# SerialRF1_SMD.net
KiCad netlist of a schematic drawn in EAGLE
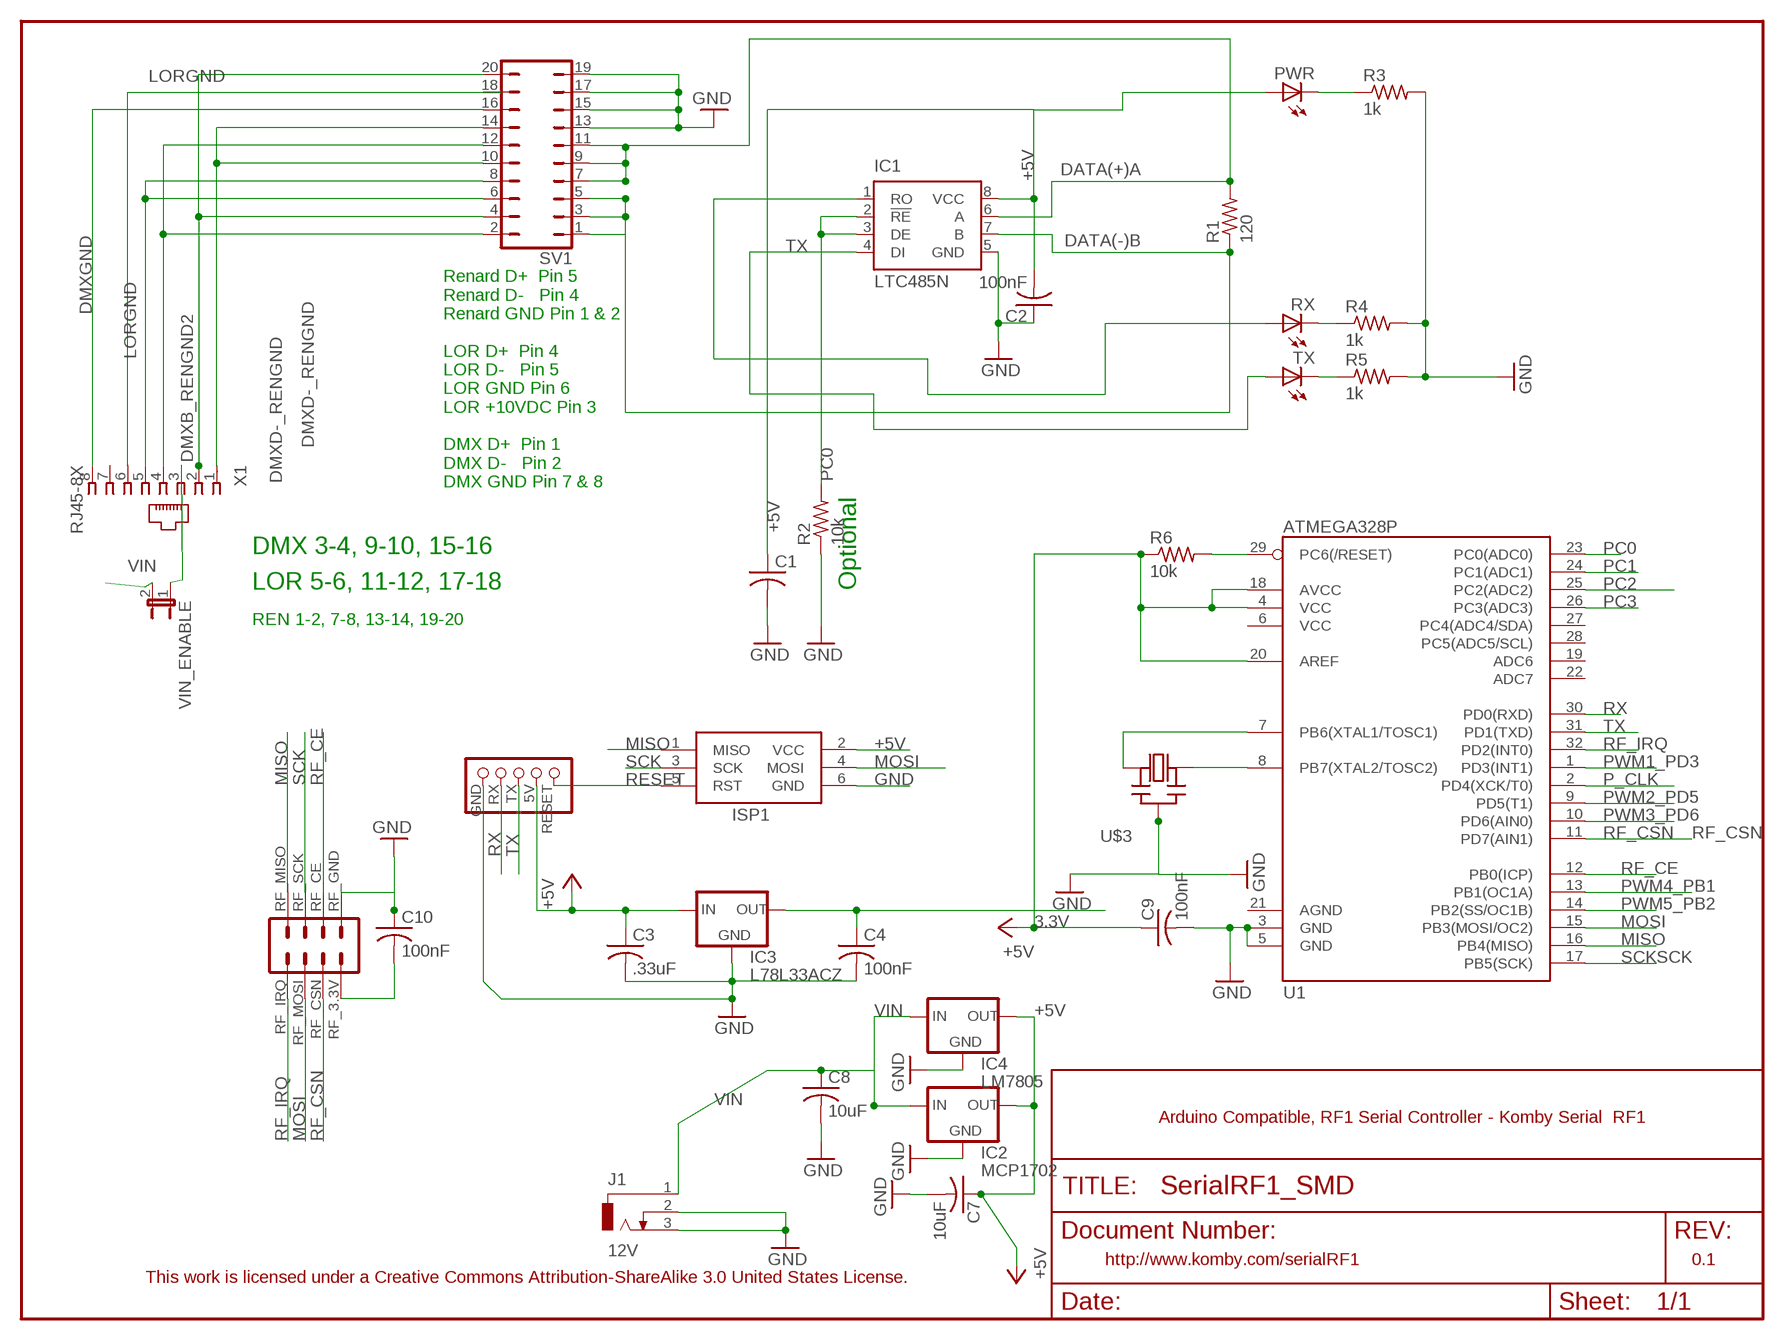
[diagram p0: schematic, sheet 1]

(export (version "E")
  (design (tool "Eeschema 10.0.6"))
  (components
    (comp (ref "C1")
      (value "C-USC0805K")
      (footprint "eagle-import:C0805K")
      (libsource (lib "eagle-import") (part "C-USC0805K"))
    )
    (comp (ref "C2")
      (value "100nF")
      (footprint "eagle-import:C0805K")
      (libsource (lib "eagle-import") (part "C-USC0805K"))
    )
    (comp (ref "C3")
      (value ".33uF")
      (footprint "eagle-import:C0805K")
      (libsource (lib "eagle-import") (part "C-USC0805K"))
    )
    (comp (ref "C4")
      (value "100nF")
      (footprint "eagle-import:C0805K")
      (libsource (lib "eagle-import") (part "C-USC0805K"))
    )
    (comp (ref "C7")
      (value "10uF")
      (footprint "eagle-import:C0805K")
      (libsource (lib "eagle-import") (part "C-USC0805K"))
    )
    (comp (ref "C8")
      (value "10uF")
      (footprint "eagle-import:C0805K")
      (libsource (lib "eagle-import") (part "C-USC0805K"))
    )
    (comp (ref "C9")
      (value "100nF")
      (footprint "eagle-import:C0805K")
      (libsource (lib "eagle-import") (part "C-USC0805K"))
    )
    (comp (ref "C10")
      (value "100nF")
      (footprint "eagle-import:C0805K")
      (libsource (lib "eagle-import") (part "C-USC0805K"))
    )
    (comp (ref "IC1")
      (value "LTC485N")
      (footprint "eagle-import:DIL08")
      (libsource (lib "eagle-import") (part "LTC485N"))
    )
    (comp (ref "IC2")
      (value "MCP1702")
      (footprint "eagle-import:TO92")
      (libsource (lib "eagle-import") (part "MCP1700TRI"))
    )
    (comp (ref "IC3")
      (value "L78L33ACZ")
      (footprint "eagle-import:78LXX")
      (libsource (lib "eagle-import") (part "78LXX"))
    )
    (comp (ref "IC4")
      (value "LM7805")
      (footprint "eagle-import:TO220-IGO")
      (libsource (lib "eagle-import") (part "V_REG_78XXSINK"))
    )
    (comp (ref "ISP1")
      (value "AVRISP-6")
      (footprint "eagle-import:AVRISP")
      (libsource (lib "eagle-import") (part "AVRISP-6"))
    )
    (comp (ref "J1")
      (value "12V")
      (footprint "eagle-import:DCJ0303")
      (libsource (lib "eagle-import") (part "DCJ0303"))
    )
    (comp (ref "PWR")
      (value "LEDSML0805")
      (footprint "eagle-import:SML0805")
      (libsource (lib "eagle-import") (part "LEDSML0805"))
    )
    (comp (ref "R1")
      (value "120")
      (footprint "eagle-import:R0805W")
      (libsource (lib "eagle-import") (part "R-US_R0805W"))
    )
    (comp (ref "R2")
      (value "10k")
      (footprint "eagle-import:R0805W")
      (libsource (lib "eagle-import") (part "R-US_R0805W"))
    )
    (comp (ref "R3")
      (value "1k")
      (footprint "eagle-import:M0805")
      (libsource (lib "eagle-import") (part "R-US_M0805"))
    )
    (comp (ref "R4")
      (value "1k")
      (footprint "eagle-import:M0805")
      (libsource (lib "eagle-import") (part "R-US_M0805"))
    )
    (comp (ref "R5")
      (value "1k")
      (footprint "eagle-import:M0805")
      (libsource (lib "eagle-import") (part "R-US_M0805"))
    )
    (comp (ref "R6")
      (value "10k")
      (footprint "eagle-import:R0805")
      (libsource (lib "eagle-import") (part "R-US_R0805"))
    )
    (comp (ref "RX")
      (value "LEDSML0805")
      (footprint "eagle-import:SML0805")
      (libsource (lib "eagle-import") (part "LEDSML0805"))
    )
    (comp (ref "SV1")
      (value "JP10Q")
      (footprint "eagle-import:JP10Q")
      (libsource (lib "eagle-import") (part "JP10Q"))
    )
    (comp (ref "TX")
      (value "LEDSML0805")
      (footprint "eagle-import:SML0805")
      (libsource (lib "eagle-import") (part "LEDSML0805"))
    )
    (comp (ref "U$3")
      (value "CERMOSCILL-THM")
      (footprint "eagle-import:CERM_OSC")
      (libsource (lib "eagle-import") (part "CERMOSCILL-THM"))
    )
    (comp (ref "U$4")
      (value "KOMBY_TTL_SERIAL")
      (footprint "eagle-import:KOMBY_SERIAL_FOOTPRINT")
      (libsource (lib "eagle-import") (part "KOMBY_TTL_SERIAL"))
    )
    (comp (ref "U$6")
      (value "NRF24L01_HEADER")
      (footprint "eagle-import:NRF24L01")
      (libsource (lib "eagle-import") (part "NRF24L01_HEADER"))
    )
    (comp (ref "U1")
      (value "ATMEGA328P")
      (footprint "eagle-import:TQFP32-08")
      (libsource (lib "eagle-import") (part "ATMEGA328_SMT"))
    )
    (comp (ref "VIN_ENABLE")
      (value "JP1E")
      (footprint "eagle-import:JP1")
      (libsource (lib "eagle-import") (part "JP1E"))
    )
    (comp (ref "X1")
      (value "RJ45-8X")
      (footprint "eagle-import:RJ45-NO-SHIELD")
      (libsource (lib "eagle-import") (part "RJ45-8X"))
    )
  )
  (nets
    (net (code "1") (name "+5V") (class "Default")
      (node (ref "C1") (pin "1") (pinfunction "1_1") (pintype "passive"))
      (node (ref "C2") (pin "2") (pinfunction "2_2") (pintype "passive"))
      (node (ref "C3") (pin "1") (pinfunction "1_1") (pintype "passive"))
      (node (ref "C7") (pin "1") (pinfunction "1_1") (pintype "passive"))
      (node (ref "C9") (pin "1") (pinfunction "1_1") (pintype "passive"))
      (node (ref "IC1") (pin "8") (pinfunction "VCC_8") (pintype "input"))
      (node (ref "IC2") (pin "3") (pinfunction "OUT_3") (pintype "passive"))
      (node (ref "IC3") (pin "IN") (pinfunction "IN_IN") (pintype "input"))
      (node (ref "IC4") (pin "OUT") (pinfunction "OUT_OUT") (pintype "output"))
      (node (ref "ISP1") (pin "2") (pinfunction "VCC_2") (pintype "power_in"))
      (node (ref "PWR") (pin "A") (pinfunction "A_A") (pintype "passive"))
      (node (ref "R6") (pin "1") (pinfunction "1_1") (pintype "passive"))
      (node (ref "U$4") (pin "5V") (pinfunction "5V_5V") (pintype "passive"))
      (node (ref "U1") (pin "18") (pinfunction "AVCC_18") (pintype "bidirectional"))
      (node (ref "U1") (pin "20") (pinfunction "AREF_20") (pintype "bidirectional"))
      (node (ref "U1") (pin "4") (pinfunction "VCC_4") (pintype "bidirectional"))
    )
    (net (code "2") (name "/3.3V") (class "Default")
      (node (ref "C4") (pin "1") (pinfunction "1_1") (pintype "passive"))
      (node (ref "IC3") (pin "OUT") (pinfunction "OUT_OUT") (pintype "passive"))
    )
    (net (code "3") (name "/DATA(+)A") (class "Default")
      (node (ref "IC1") (pin "6") (pinfunction "A_6") (pintype "bidirectional"))
      (node (ref "R1") (pin "2") (pinfunction "2_2") (pintype "passive"))
      (node (ref "SV1") (pin "11") (pinfunction "11_11") (pintype "passive"))
      (node (ref "SV1") (pin "7") (pinfunction "7_7") (pintype "passive"))
      (node (ref "SV1") (pin "9") (pinfunction "9_9") (pintype "passive"))
    )
    (net (code "4") (name "/DATA(-)B") (class "Default")
      (node (ref "IC1") (pin "7") (pinfunction "B_7") (pintype "bidirectional"))
      (node (ref "R1") (pin "1") (pinfunction "1_1") (pintype "passive"))
      (node (ref "SV1") (pin "1") (pinfunction "1_1") (pintype "passive"))
      (node (ref "SV1") (pin "3") (pinfunction "3_3") (pintype "passive"))
      (node (ref "SV1") (pin "5") (pinfunction "5_5") (pintype "passive"))
    )
    (net (code "5") (name "/DMXB_RENGND2") (class "Default")
      (node (ref "SV1") (pin "20") (pinfunction "20_20") (pintype "passive"))
      (node (ref "SV1") (pin "4") (pinfunction "4_4") (pintype "passive"))
      (node (ref "X1") (pin "2") (pinfunction "2_2") (pintype "passive"))
    )
    (net (code "6") (name "/DMXD-_RENGND") (class "Default")
      (node (ref "SV1") (pin "10") (pinfunction "10_10") (pintype "passive"))
      (node (ref "SV1") (pin "14") (pinfunction "14_14") (pintype "passive"))
      (node (ref "X1") (pin "1") (pinfunction "1_1") (pintype "passive"))
    )
    (net (code "7") (name "/DMXGND") (class "Default")
      (node (ref "SV1") (pin "16") (pinfunction "16_16") (pintype "passive"))
      (node (ref "X1") (pin "8") (pinfunction "8_8") (pintype "passive"))
    )
    (net (code "8") (name "/LORGND") (class "Default")
      (node (ref "SV1") (pin "18") (pinfunction "18_18") (pintype "passive"))
      (node (ref "X1") (pin "6") (pinfunction "6_6") (pintype "passive"))
    )
    (net (code "9") (name "/MISO") (class "Default")
      (node (ref "ISP1") (pin "1") (pinfunction "MISO_1") (pintype "input"))
      (node (ref "U$6") (pin "RF_MISO") (pinfunction "RF_MISO_RF_MISO") (pintype "passive"))
      (node (ref "U1") (pin "16") (pinfunction "PB4(MISO)_16") (pintype "bidirectional"))
    )
    (net (code "10") (name "/MOSI") (class "Default")
      (node (ref "ISP1") (pin "4") (pinfunction "MOSI_4") (pintype "output"))
      (node (ref "U$6") (pin "RF_MOSI") (pinfunction "RF_MOSI_RF_MOSI") (pintype "passive"))
      (node (ref "U1") (pin "15") (pinfunction "PB3(MOSI/OC2)_15") (pintype "bidirectional"))
    )
    (net (code "11") (name "/PC0") (class "Default")
      (node (ref "IC1") (pin "2") (pinfunction "~{RE}_2") (pintype "input"))
      (node (ref "IC1") (pin "3") (pinfunction "DE_3") (pintype "input"))
      (node (ref "R2") (pin "2") (pinfunction "2_2") (pintype "passive"))
      (node (ref "U1") (pin "23") (pinfunction "PC0(ADC0)_23") (pintype "bidirectional"))
    )
    (net (code "12") (name "/PC1") (class "Default")
      (node (ref "U1") (pin "24") (pinfunction "PC1(ADC1)_24") (pintype "bidirectional"))
    )
    (net (code "13") (name "/PC2") (class "Default")
      (node (ref "U1") (pin "25") (pinfunction "PC2(ADC2)_25") (pintype "bidirectional"))
    )
    (net (code "14") (name "/PC3") (class "Default")
      (node (ref "U1") (pin "26") (pinfunction "PC3(ADC3)_26") (pintype "bidirectional"))
    )
    (net (code "15") (name "/PWM1_PD3") (class "Default")
      (node (ref "U1") (pin "1") (pinfunction "PD3(INT1)_1") (pintype "bidirectional"))
    )
    (net (code "16") (name "/PWM2_PD5") (class "Default")
      (node (ref "U1") (pin "9") (pinfunction "PD5(T1)_9") (pintype "bidirectional"))
    )
    (net (code "17") (name "/PWM3_PD6") (class "Default")
      (node (ref "U1") (pin "10") (pinfunction "PD6(AIN0)_10") (pintype "bidirectional"))
    )
    (net (code "18") (name "/PWM4_PB1") (class "Default")
      (node (ref "U1") (pin "13") (pinfunction "PB1(OC1A)_13") (pintype "bidirectional"))
    )
    (net (code "19") (name "/PWM5_PB2") (class "Default")
      (node (ref "U1") (pin "14") (pinfunction "PB2(SS/OC1B)_14") (pintype "bidirectional"))
    )
    (net (code "20") (name "/P_CLK") (class "Default")
      (node (ref "U1") (pin "2") (pinfunction "PD4(XCK/T0)_2") (pintype "bidirectional"))
    )
    (net (code "21") (name "/RESET") (class "Default")
      (node (ref "ISP1") (pin "5") (pinfunction "RST_5") (pintype "output"))
      (node (ref "R6") (pin "2") (pinfunction "2_2") (pintype "passive"))
      (node (ref "U$4") (pin "RESET") (pinfunction "RESET_RESET") (pintype "passive"))
      (node (ref "U1") (pin "29") (pinfunction "PC6(/RESET)_29") (pintype "bidirectional"))
    )
    (net (code "22") (name "/RF_CE") (class "Default")
      (node (ref "U$6") (pin "RF_CE") (pinfunction "RF_CE_RF_CE") (pintype "passive"))
      (node (ref "U1") (pin "12") (pinfunction "PB0(ICP)_12") (pintype "bidirectional"))
    )
    (net (code "23") (name "/RF_CSN") (class "Default")
      (node (ref "U$6") (pin "RF_CSN") (pinfunction "RF_CSN_RF_CSN") (pintype "passive"))
      (node (ref "U1") (pin "11") (pinfunction "PD7(AIN1)_11") (pintype "bidirectional"))
    )
    (net (code "24") (name "/RF_IRQ") (class "Default")
      (node (ref "U$6") (pin "RF_IRQ") (pinfunction "RF_IRQ_RF_IRQ") (pintype "passive"))
      (node (ref "U1") (pin "32") (pinfunction "PD2(INT0)_32") (pintype "bidirectional"))
    )
    (net (code "25") (name "/RX") (class "Default")
      (node (ref "IC1") (pin "1") (pinfunction "RO_1") (pintype "output"))
      (node (ref "RX") (pin "A") (pinfunction "A_A") (pintype "passive"))
      (node (ref "U$4") (pin "RX") (pinfunction "RX_RX") (pintype "passive"))
      (node (ref "U1") (pin "30") (pinfunction "PD0(RXD)_30") (pintype "bidirectional"))
    )
    (net (code "26") (name "/SCK") (class "Default")
      (node (ref "ISP1") (pin "3") (pinfunction "SCK_3") (pintype "output"))
      (node (ref "U$6") (pin "RF_SCK") (pinfunction "RF_SCK_RF_SCK") (pintype "passive"))
      (node (ref "U1") (pin "17") (pinfunction "PB5(SCK)_17") (pintype "bidirectional"))
    )
    (net (code "27") (name "/TX") (class "Default")
      (node (ref "IC1") (pin "4") (pinfunction "DI_4") (pintype "input"))
      (node (ref "TX") (pin "A") (pinfunction "A_A") (pintype "passive"))
      (node (ref "U$4") (pin "TX") (pinfunction "TX_TX") (pintype "passive"))
      (node (ref "U1") (pin "31") (pinfunction "PD1(TXD)_31") (pintype "bidirectional"))
    )
    (net (code "28") (name "/VIN") (class "Default")
      (node (ref "C8") (pin "1") (pinfunction "1_1") (pintype "passive"))
      (node (ref "IC2") (pin "2") (pinfunction "IN_2") (pintype "input"))
      (node (ref "IC4") (pin "IN") (pinfunction "IN_IN") (pintype "input"))
      (node (ref "J1") (pin "1") (pinfunction "1_1") (pintype "passive"))
      (node (ref "VIN_ENABLE") (pin "2") (pinfunction "2_2") (pintype "passive"))
    )
    (net (code "29") (name "GND") (class "Default")
      (node (ref "C1") (pin "2") (pinfunction "2_2") (pintype "passive"))
      (node (ref "C10") (pin "1") (pinfunction "1_1") (pintype "passive"))
      (node (ref "C2") (pin "1") (pinfunction "1_1") (pintype "passive"))
      (node (ref "C3") (pin "2") (pinfunction "2_2") (pintype "passive"))
      (node (ref "C4") (pin "2") (pinfunction "2_2") (pintype "passive"))
      (node (ref "C7") (pin "2") (pinfunction "2_2") (pintype "passive"))
      (node (ref "C8") (pin "2") (pinfunction "2_2") (pintype "passive"))
      (node (ref "C9") (pin "2") (pinfunction "2_2") (pintype "passive"))
      (node (ref "IC1") (pin "5") (pinfunction "GND_5") (pintype "input"))
      (node (ref "IC2") (pin "1") (pinfunction "GND_1") (pintype "input"))
      (node (ref "IC3") (pin "GND") (pinfunction "GND_GND") (pintype "input"))
      (node (ref "IC4") (pin "GND") (pinfunction "GND_GND") (pintype "input"))
      (node (ref "ISP1") (pin "6") (pinfunction "GND_6") (pintype "power_in"))
      (node (ref "J1") (pin "2") (pinfunction "2_2") (pintype "passive"))
      (node (ref "J1") (pin "3") (pinfunction "3_3") (pintype "passive"))
      (node (ref "R2") (pin "1") (pinfunction "1_1") (pintype "passive"))
      (node (ref "R3") (pin "2") (pinfunction "2_2") (pintype "passive"))
      (node (ref "R4") (pin "2") (pinfunction "2_2") (pintype "passive"))
      (node (ref "R5") (pin "2") (pinfunction "2_2") (pintype "passive"))
      (node (ref "SV1") (pin "13") (pinfunction "13_13") (pintype "passive"))
      (node (ref "SV1") (pin "15") (pinfunction "15_15") (pintype "passive"))
      (node (ref "SV1") (pin "17") (pinfunction "17_17") (pintype "passive"))
      (node (ref "SV1") (pin "19") (pinfunction "19_19") (pintype "passive"))
      (node (ref "U$3") (pin "P$2") (pinfunction "GND_P$2") (pintype "bidirectional"))
      (node (ref "U$4") (pin "GND") (pinfunction "GND_GND") (pintype "passive"))
      (node (ref "U$6") (pin "RF_GND") (pinfunction "RFGND_1_RF_GND") (pintype "passive"))
      (node (ref "U1") (pin "3") (pinfunction "GND_3") (pintype "bidirectional"))
      (node (ref "U1") (pin "5") (pinfunction "GND_5") (pintype "bidirectional"))
    )
    (net (code "30") (name "Net-(C10-Pad2)") (class "Default")
      (node (ref "C10") (pin "2") (pinfunction "2_2") (pintype "passive"))
      (node (ref "U$6") (pin "RF_3.3V") (pinfunction "RF_3.3V_RF_3.3V") (pintype "passive"))
    )
    (net (code "31") (name "Net-(PWR-PadC)") (class "Default")
      (node (ref "PWR") (pin "C") (pinfunction "C_C") (pintype "passive"))
      (node (ref "R3") (pin "1") (pinfunction "1_1") (pintype "passive"))
    )
    (net (code "32") (name "Net-(R4-Pad1)") (class "Default")
      (node (ref "R4") (pin "1") (pinfunction "1_1") (pintype "passive"))
      (node (ref "RX") (pin "C") (pinfunction "C_C") (pintype "passive"))
    )
    (net (code "33") (name "Net-(R5-Pad1)") (class "Default")
      (node (ref "R5") (pin "1") (pinfunction "1_1") (pintype "passive"))
      (node (ref "TX") (pin "C") (pinfunction "C_C") (pintype "passive"))
    )
    (net (code "34") (name "Net-(SV1-Pad6)") (class "Default")
      (node (ref "SV1") (pin "6") (pinfunction "6_6") (pintype "passive"))
      (node (ref "SV1") (pin "8") (pinfunction "8_8") (pintype "passive"))
      (node (ref "X1") (pin "5") (pinfunction "5_5") (pintype "passive"))
    )
    (net (code "35") (name "Net-(SV1-Pad12)") (class "Default")
      (node (ref "SV1") (pin "12") (pinfunction "12_12") (pintype "passive"))
      (node (ref "SV1") (pin "2") (pinfunction "2_2") (pintype "passive"))
      (node (ref "X1") (pin "4") (pinfunction "4_4") (pintype "passive"))
    )
    (net (code "36") (name "Net-(U$3-IN)") (class "Default")
      (node (ref "U$3") (pin "P$1") (pinfunction "IN_P$1") (pintype "bidirectional"))
      (node (ref "U1") (pin "7") (pinfunction "PB6(XTAL1/TOSC1)_7") (pintype "bidirectional"))
    )
    (net (code "37") (name "Net-(U$3-OUT)") (class "Default")
      (node (ref "U$3") (pin "P$3") (pinfunction "OUT_P$3") (pintype "bidirectional"))
      (node (ref "U1") (pin "8") (pinfunction "PB7(XTAL2/TOSC2)_8") (pintype "bidirectional"))
    )
    (net (code "38") (name "Net-(VIN_ENABLE-Pad1)") (class "Default")
      (node (ref "VIN_ENABLE") (pin "1") (pinfunction "1_1") (pintype "passive"))
      (node (ref "X1") (pin "3") (pinfunction "3_3") (pintype "passive"))
    )
    (net (code "39") (name "unconnected-(U1-ADC6-Pad19)") (class "Default")
      (node (ref "U1") (pin "19") (pinfunction "ADC6_19") (pintype "bidirectional"))
    )
    (net (code "40") (name "unconnected-(U1-ADC7-Pad22)") (class "Default")
      (node (ref "U1") (pin "22") (pinfunction "ADC7_22") (pintype "bidirectional"))
    )
    (net (code "41") (name "unconnected-(U1-AGND-Pad21)") (class "Default")
      (node (ref "U1") (pin "21") (pinfunction "AGND_21") (pintype "bidirectional"))
    )
    (net (code "42") (name "unconnected-(U1-PC4(ADC4{slash}SDA)-Pad27)") (class "Default")
      (node (ref "U1") (pin "27") (pinfunction "PC4(ADC4/SDA)_27") (pintype "bidirectional"))
    )
    (net (code "43") (name "unconnected-(U1-PC5(ADC5{slash}SCL)-Pad28)") (class "Default")
      (node (ref "U1") (pin "28") (pinfunction "PC5(ADC5/SCL)_28") (pintype "bidirectional"))
    )
    (net (code "44") (name "unconnected-(U1-VCC-Pad6)") (class "Default")
      (node (ref "U1") (pin "6") (pinfunction "VCC_6") (pintype "bidirectional"))
    )
    (net (code "45") (name "unconnected-(X1-Pad7)") (class "Default")
      (node (ref "X1") (pin "7") (pinfunction "7_7") (pintype "passive"))
    )
  )
)
